# untitled.net
KiCad netlist of a schematic drawn in EAGLE
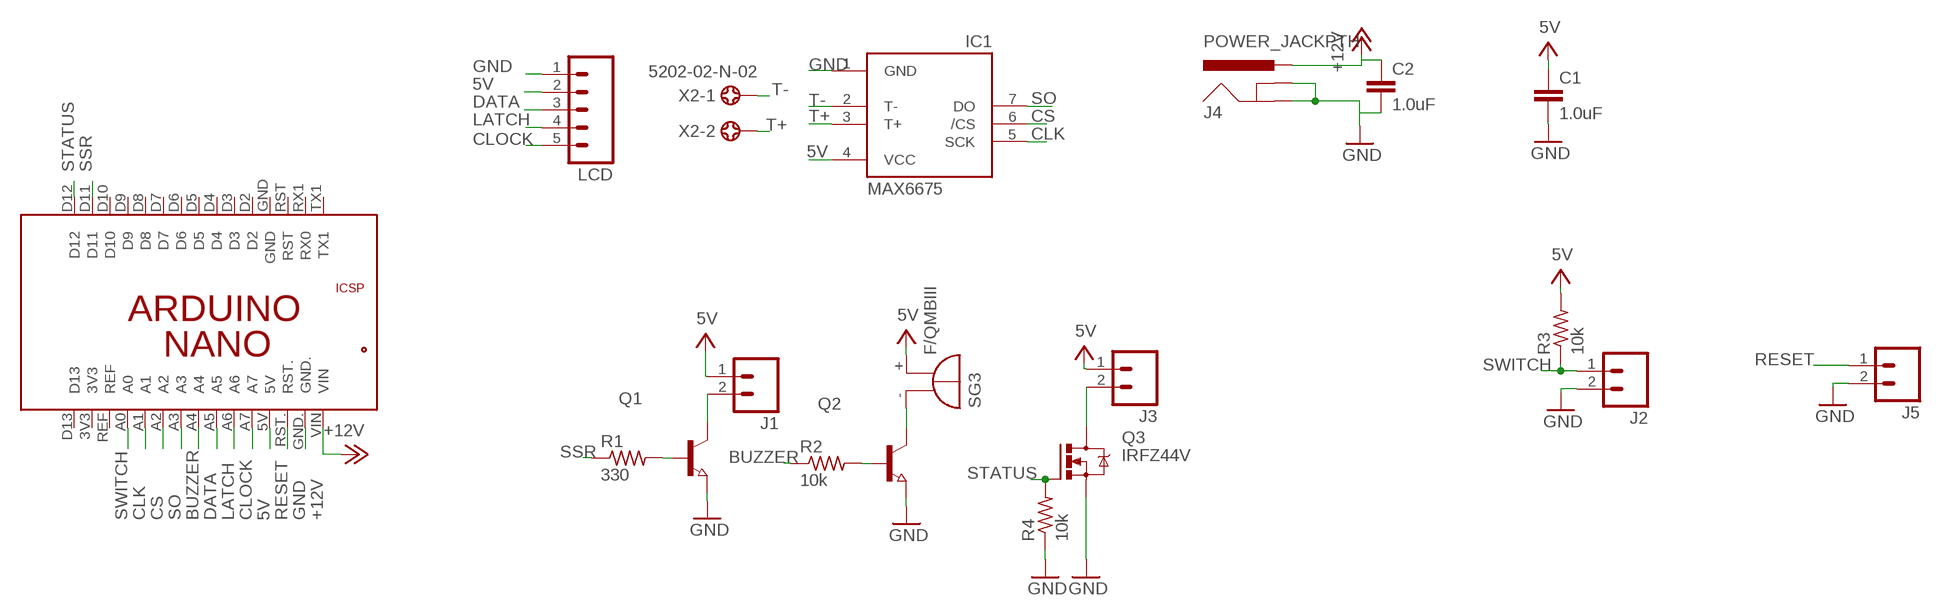
[diagram p0: schematic, sheet 1]

(export (version "E")
  (design (tool "Eeschema 10.0.6"))
  (components
    (comp (ref "C1")
      (value "1.0uF")
      (footprint "eagle-import:1206-CAP")
      (libsource (lib "eagle-import") (part "1.0UF50V10%(1206)"))
    )
    (comp (ref "C2")
      (value "1.0uF")
      (footprint "eagle-import:1206-CAP")
      (libsource (lib "eagle-import") (part "1.0UF50V10%(1206)"))
    )
    (comp (ref "IC1")
      (value "MAX6675")
      (footprint "eagle-import:SO08")
      (libsource (lib "eagle-import") (part "MAX6675"))
    )
    (comp (ref "J1")
      (value "M02PTH")
      (footprint "eagle-import:1X02")
      (libsource (lib "eagle-import") (part "M02PTH"))
    )
    (comp (ref "J2")
      (value "M02PTH")
      (footprint "eagle-import:1X02")
      (libsource (lib "eagle-import") (part "M02PTH"))
    )
    (comp (ref "J3")
      (value "M02PTH")
      (footprint "eagle-import:1X02")
      (libsource (lib "eagle-import") (part "M02PTH"))
    )
    (comp (ref "J4")
      (value "POWER_JACKPTH")
      (footprint "eagle-import:POWER_JACK_PTH")
      (libsource (lib "eagle-import") (part "POWER_JACKPTH"))
    )
    (comp (ref "J5")
      (value "M02PTH")
      (footprint "eagle-import:1X02")
      (libsource (lib "eagle-import") (part "M02PTH"))
    )
    (comp (ref "LCD")
      (value "M05PTH")
      (footprint "eagle-import:1X05")
      (libsource (lib "eagle-import") (part "M05PTH"))
    )
    (comp (ref "PCB2")
      (value "ARDUINO_NANO_RHEYD")
      (footprint "eagle-import:ARDUINO_NANO")
      (libsource (lib "eagle-import") (part "ARDUINO_NANO_RHEYD"))
    )
    (comp (ref "Q1")
      (value "NPN-TRANSISTOR_SOT23")
      (footprint "eagle-import:SOT23")
      (libsource (lib "eagle-import") (part "NPN-TRANSISTOR_SOT23"))
    )
    (comp (ref "Q2")
      (value "NPN-TRANSISTOR_SOT23")
      (footprint "eagle-import:SOT23")
      (libsource (lib "eagle-import") (part "NPN-TRANSISTOR_SOT23"))
    )
    (comp (ref "Q3")
      (value "IRFZ44V")
      (footprint "eagle-import:TO220BH")
      (libsource (lib "eagle-import") (part "IRFZ48Z"))
    )
    (comp (ref "R1")
      (value "330")
      (footprint "eagle-import:R1206")
      (libsource (lib "eagle-import") (part "R-US_R1206"))
    )
    (comp (ref "R2")
      (value "10k")
      (footprint "eagle-import:R1206")
      (libsource (lib "eagle-import") (part "R-US_R1206"))
    )
    (comp (ref "R3")
      (value "10k")
      (footprint "eagle-import:R1206")
      (libsource (lib "eagle-import") (part "R-US_R1206"))
    )
    (comp (ref "R4")
      (value "10k")
      (footprint "eagle-import:R1206")
      (libsource (lib "eagle-import") (part "R-US_R1206"))
    )
    (comp (ref "SG3")
      (value "F/QMBIII")
      (footprint "eagle-import:F_QMBIII")
      (libsource (lib "eagle-import") (part "F/QMBIII"))
    )
    (comp (ref "X2")
      (value "5202-02-N-02")
      (footprint "eagle-import:5202-02-N-02")
      (libsource (lib "eagle-import") (part "5202-02-N-02"))
    )
  )
  (nets
    (net (code "1") (name "+12V") (class "Default")
      (node (ref "C2") (pin "1") (pinfunction "1_1") (pintype "passive"))
      (node (ref "J4") (pin "PWR") (pinfunction "PWR_PWR") (pintype "bidirectional"))
      (node (ref "PCB2") (pin "VIN") (pinfunction "VIN_VIN") (pintype "bidirectional"))
    )
    (net (code "2") (name "/BUZZER") (class "Default")
      (node (ref "PCB2") (pin "A4") (pinfunction "A4_A4") (pintype "bidirectional"))
      (node (ref "R2") (pin "1") (pinfunction "1_1") (pintype "passive"))
    )
    (net (code "3") (name "/CLK") (class "Default")
      (node (ref "IC1") (pin "5") (pinfunction "SCK_5") (pintype "input"))
      (node (ref "PCB2") (pin "A1") (pinfunction "A1_A1") (pintype "bidirectional"))
    )
    (net (code "4") (name "/CLOCK") (class "Default")
      (node (ref "LCD") (pin "5") (pinfunction "5_5") (pintype "passive"))
      (node (ref "PCB2") (pin "A7") (pinfunction "A7_A7") (pintype "bidirectional"))
    )
    (net (code "5") (name "/CS") (class "Default")
      (node (ref "IC1") (pin "6") (pinfunction "/CS_6") (pintype "input"))
      (node (ref "PCB2") (pin "A2") (pinfunction "A2_A2") (pintype "bidirectional"))
    )
    (net (code "6") (name "/DATA") (class "Default")
      (node (ref "LCD") (pin "3") (pinfunction "3_3") (pintype "passive"))
      (node (ref "PCB2") (pin "A5") (pinfunction "A5_A5") (pintype "bidirectional"))
    )
    (net (code "7") (name "/LATCH") (class "Default")
      (node (ref "LCD") (pin "4") (pinfunction "4_4") (pintype "passive"))
      (node (ref "PCB2") (pin "A6") (pinfunction "A6_A6") (pintype "bidirectional"))
    )
    (net (code "8") (name "/RESET") (class "Default")
      (node (ref "J5") (pin "1") (pinfunction "1_1") (pintype "passive"))
      (node (ref "PCB2") (pin "RST.") (pinfunction "RST._RST.") (pintype "bidirectional"))
    )
    (net (code "9") (name "/SO") (class "Default")
      (node (ref "IC1") (pin "7") (pinfunction "DO_7") (pintype "output"))
      (node (ref "PCB2") (pin "A3") (pinfunction "A3_A3") (pintype "bidirectional"))
    )
    (net (code "10") (name "/SSR") (class "Default")
      (node (ref "PCB2") (pin "D11") (pinfunction "D11_D11") (pintype "bidirectional"))
      (node (ref "R1") (pin "1") (pinfunction "1_1") (pintype "passive"))
    )
    (net (code "11") (name "/STATUS") (class "Default")
      (node (ref "PCB2") (pin "D12") (pinfunction "D12_D12") (pintype "bidirectional"))
      (node (ref "Q3") (pin "G") (pinfunction "G_G") (pintype "passive"))
      (node (ref "R4") (pin "2") (pinfunction "2_2") (pintype "passive"))
    )
    (net (code "12") (name "/SWITCH") (class "Default")
      (node (ref "J2") (pin "1") (pinfunction "1_1") (pintype "passive"))
      (node (ref "PCB2") (pin "A0") (pinfunction "A0_A0") (pintype "bidirectional"))
      (node (ref "R3") (pin "1") (pinfunction "1_1") (pintype "passive"))
    )
    (net (code "13") (name "/T+") (class "Default")
      (node (ref "IC1") (pin "3") (pinfunction "T+_3") (pintype "input"))
      (node (ref "X2") (pin "2") (pinfunction "1_2") (pintype "passive"))
    )
    (net (code "14") (name "/T-") (class "Default")
      (node (ref "IC1") (pin "2") (pinfunction "T-_2") (pintype "input"))
      (node (ref "X2") (pin "1") (pinfunction "1_1") (pintype "passive"))
    )
    (net (code "15") (name "5V") (class "Default")
      (node (ref "C1") (pin "1") (pinfunction "1_1") (pintype "passive"))
      (node (ref "IC1") (pin "4") (pinfunction "VCC_4") (pintype "power_in"))
      (node (ref "J1") (pin "1") (pinfunction "1_1") (pintype "passive"))
      (node (ref "J3") (pin "1") (pinfunction "1_1") (pintype "passive"))
      (node (ref "LCD") (pin "2") (pinfunction "2_2") (pintype "passive"))
      (node (ref "PCB2") (pin "5V") (pinfunction "5V_5V") (pintype "bidirectional"))
      (node (ref "R3") (pin "2") (pinfunction "2_2") (pintype "passive"))
      (node (ref "SG3") (pin "+") (pinfunction "-_+") (pintype "passive"))
    )
    (net (code "16") (name "GND") (class "Default")
      (node (ref "C1") (pin "2") (pinfunction "2_2") (pintype "passive"))
      (node (ref "C2") (pin "2") (pinfunction "2_2") (pintype "passive"))
      (node (ref "IC1") (pin "1") (pinfunction "GND_1") (pintype "power_in"))
      (node (ref "J2") (pin "2") (pinfunction "2_2") (pintype "passive"))
      (node (ref "J4") (pin "GND") (pinfunction "GND_GND") (pintype "bidirectional"))
      (node (ref "J4") (pin "GNDBREAK") (pinfunction "GNDBREAK_GNDBREAK") (pintype "bidirectional"))
      (node (ref "J5") (pin "2") (pinfunction "2_2") (pintype "passive"))
      (node (ref "LCD") (pin "1") (pinfunction "1_1") (pintype "passive"))
      (node (ref "PCB2") (pin "GND.") (pinfunction "GND._GND.") (pintype "bidirectional"))
      (node (ref "Q1") (pin "2") (pinfunction "E_2") (pintype "passive"))
      (node (ref "Q2") (pin "2") (pinfunction "E_2") (pintype "passive"))
      (node (ref "Q3") (pin "S") (pinfunction "S_S") (pintype "passive"))
      (node (ref "R4") (pin "1") (pinfunction "1_1") (pintype "passive"))
    )
    (net (code "17") (name "Net-(J3-Pad2)") (class "Default")
      (node (ref "J3") (pin "2") (pinfunction "2_2") (pintype "passive"))
      (node (ref "Q3") (pin "D") (pinfunction "D_D") (pintype "passive"))
    )
    (net (code "18") (name "Net-(Q1-B)") (class "Default")
      (node (ref "Q1") (pin "1") (pinfunction "B_1") (pintype "passive"))
      (node (ref "R1") (pin "2") (pinfunction "2_2") (pintype "passive"))
    )
    (net (code "19") (name "Net-(Q1-C)") (class "Default")
      (node (ref "J1") (pin "2") (pinfunction "2_2") (pintype "passive"))
      (node (ref "Q1") (pin "3") (pinfunction "C_3") (pintype "passive"))
    )
    (net (code "20") (name "Net-(Q2-B)") (class "Default")
      (node (ref "Q2") (pin "1") (pinfunction "B_1") (pintype "passive"))
      (node (ref "R2") (pin "2") (pinfunction "2_2") (pintype "passive"))
    )
    (net (code "21") (name "Net-(Q2-C)") (class "Default")
      (node (ref "Q2") (pin "3") (pinfunction "C_3") (pintype "passive"))
      (node (ref "SG3") (pin "-") (pinfunction "+_-") (pintype "passive"))
    )
    (net (code "22") (name "unconnected-(PCB2-Pad3V3)") (class "Default")
      (node (ref "PCB2") (pin "3V3") (pinfunction "3V3_3V3") (pintype "bidirectional"))
    )
    (net (code "23") (name "unconnected-(PCB2-PadD2)") (class "Default")
      (node (ref "PCB2") (pin "D2") (pinfunction "D2_D2") (pintype "bidirectional"))
    )
    (net (code "24") (name "unconnected-(PCB2-PadD3)") (class "Default")
      (node (ref "PCB2") (pin "D3") (pinfunction "D3_D3") (pintype "bidirectional"))
    )
    (net (code "25") (name "unconnected-(PCB2-PadD4)") (class "Default")
      (node (ref "PCB2") (pin "D4") (pinfunction "D4_D4") (pintype "bidirectional"))
    )
    (net (code "26") (name "unconnected-(PCB2-PadD5)") (class "Default")
      (node (ref "PCB2") (pin "D5") (pinfunction "D5_D5") (pintype "bidirectional"))
    )
    (net (code "27") (name "unconnected-(PCB2-PadD6)") (class "Default")
      (node (ref "PCB2") (pin "D6") (pinfunction "D6_D6") (pintype "bidirectional"))
    )
    (net (code "28") (name "unconnected-(PCB2-PadD7)") (class "Default")
      (node (ref "PCB2") (pin "D7") (pinfunction "D7_D7") (pintype "bidirectional"))
    )
    (net (code "29") (name "unconnected-(PCB2-PadD8)") (class "Default")
      (node (ref "PCB2") (pin "D8") (pinfunction "D8_D8") (pintype "bidirectional"))
    )
    (net (code "30") (name "unconnected-(PCB2-PadD9)") (class "Default")
      (node (ref "PCB2") (pin "D9") (pinfunction "D9_D9") (pintype "bidirectional"))
    )
    (net (code "31") (name "unconnected-(PCB2-PadD10)") (class "Default")
      (node (ref "PCB2") (pin "D10") (pinfunction "D10_D10") (pintype "bidirectional"))
    )
    (net (code "32") (name "unconnected-(PCB2-PadD13)") (class "Default")
      (node (ref "PCB2") (pin "D13") (pinfunction "D13_D13") (pintype "bidirectional"))
    )
    (net (code "33") (name "unconnected-(PCB2-PadGND)") (class "Default")
      (node (ref "PCB2") (pin "GND") (pinfunction "GND_GND") (pintype "bidirectional"))
    )
    (net (code "34") (name "unconnected-(PCB2-PadREF)") (class "Default")
      (node (ref "PCB2") (pin "REF") (pinfunction "REF_REF") (pintype "bidirectional"))
    )
    (net (code "35") (name "unconnected-(PCB2-PadRST)") (class "Default")
      (node (ref "PCB2") (pin "RST") (pinfunction "RST_RST") (pintype "bidirectional"))
    )
    (net (code "36") (name "unconnected-(PCB2-PadTX1)") (class "Default")
      (node (ref "PCB2") (pin "TX1") (pinfunction "TX1_TX1") (pintype "bidirectional"))
    )
    (net (code "37") (name "unconnected-(PCB2-RX0-PadRX1)") (class "Default")
      (node (ref "PCB2") (pin "RX1") (pinfunction "RX0_RX1") (pintype "bidirectional"))
    )
  )
)
